# SPI_Relays.net
KiCad netlist of a schematic drawn in Altium Designer
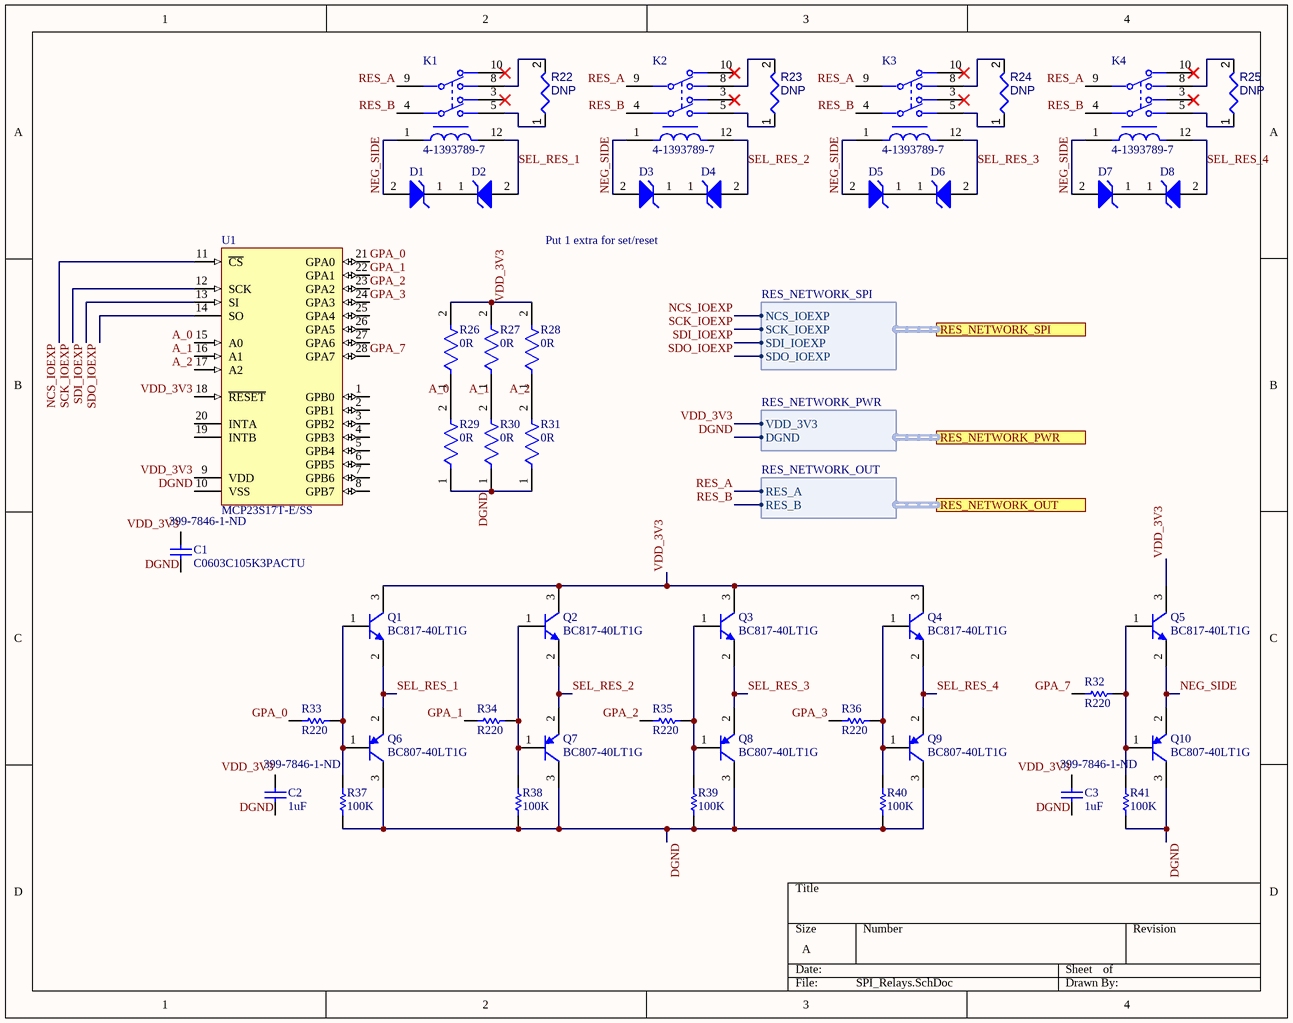
[diagram p0: SPI_Relays.SchDoc]

(export (version "E")
  (design (tool "Eeschema 10.0.6"))
  (components
    (comp (ref "C1")
      (value "C0603C105K3PACTU")
      (footprint "CAPC1608X95X35LL15T15")
      (fields
        (field (name "MANUFACTURER") "Kemet")
        (field (name "SUPPLIER PART NUMBER 1") "399-7846-1-ND")
        (field (name "TOLERANCE") "10%")
        (field (name "VOLTAGE") "25V")
      )
      (libsource (lib "Altium Content Vault") (part "CAP"))
    )
    (comp (ref "C2")
      (value "1uF")
      (footprint "CAPC1608X95X35LL15T15")
      (fields
        (field (name "MANUFACTURER") "Kemet")
        (field (name "PART NUMBER") "C0603C105K3PACTU")
        (field (name "SUPPLIER PART NUMBER 1") "399-7846-1-ND")
        (field (name "TOLERANCE") "10%")
      )
      (libsource (lib "Altium Content Vault") (part "CAP"))
    )
    (comp (ref "C3")
      (value "1uF")
      (footprint "CAPC1608X95X35LL15T15")
      (fields
        (field (name "MANUFACTURER") "Kemet")
        (field (name "PART NUMBER") "C0603C105K3PACTU")
        (field (name "SUPPLIER PART NUMBER 1") "399-7846-1-ND")
        (field (name "TOLERANCE") "10%")
      )
      (libsource (lib "Altium Content Vault") (part "CAP"))
    )
    (comp (ref "D1")
      (value "SZMM3Z6V2T1G")
      (footprint "ONSC-SOD-323-2-477-02_V")
      (description "Zener Voltage Regulator, 300 mW, 2-Pin SOD-323, Pb-Free, Tape and Reel")
      (fields (field (name "MANUFACTURER") "On Semiconductor"))
      (libsource (lib "Altium Content Vault") (part "ONSC-K1A2-2"))
    )
    (comp (ref "D2")
      (value "SZMM3Z6V2T1G")
      (footprint "ONSC-SOD-323-2-477-02_V")
      (description "Zener Voltage Regulator, 300 mW, 2-Pin SOD-323, Pb-Free, Tape and Reel")
      (fields (field (name "MANUFACTURER") "On Semiconductor"))
      (libsource (lib "Altium Content Vault") (part "ONSC-K1A2-2"))
    )
    (comp (ref "D3")
      (value "SZMM3Z6V2T1G")
      (footprint "ONSC-SOD-323-2-477-02_V")
      (description "Zener Voltage Regulator, 300 mW, 2-Pin SOD-323, Pb-Free, Tape and Reel")
      (fields (field (name "MANUFACTURER") "On Semiconductor"))
      (libsource (lib "Altium Content Vault") (part "ONSC-K1A2-2"))
    )
    (comp (ref "D4")
      (value "SZMM3Z6V2T1G")
      (footprint "ONSC-SOD-323-2-477-02_V")
      (description "Zener Voltage Regulator, 300 mW, 2-Pin SOD-323, Pb-Free, Tape and Reel")
      (fields (field (name "MANUFACTURER") "On Semiconductor"))
      (libsource (lib "Altium Content Vault") (part "ONSC-K1A2-2"))
    )
    (comp (ref "D5")
      (value "SZMM3Z6V2T1G")
      (footprint "ONSC-SOD-323-2-477-02_V")
      (description "Zener Voltage Regulator, 300 mW, 2-Pin SOD-323, Pb-Free, Tape and Reel")
      (fields (field (name "MANUFACTURER") "On Semiconductor"))
      (libsource (lib "Altium Content Vault") (part "ONSC-K1A2-2"))
    )
    (comp (ref "D6")
      (value "SZMM3Z6V2T1G")
      (footprint "ONSC-SOD-323-2-477-02_V")
      (description "Zener Voltage Regulator, 300 mW, 2-Pin SOD-323, Pb-Free, Tape and Reel")
      (fields (field (name "MANUFACTURER") "On Semiconductor"))
      (libsource (lib "Altium Content Vault") (part "ONSC-K1A2-2"))
    )
    (comp (ref "D7")
      (value "SZMM3Z6V2T1G")
      (footprint "ONSC-SOD-323-2-477-02_V")
      (description "Zener Voltage Regulator, 300 mW, 2-Pin SOD-323, Pb-Free, Tape and Reel")
      (fields (field (name "MANUFACTURER") "On Semiconductor"))
      (libsource (lib "Altium Content Vault") (part "ONSC-K1A2-2"))
    )
    (comp (ref "D8")
      (value "SZMM3Z6V2T1G")
      (footprint "ONSC-SOD-323-2-477-02_V")
      (description "Zener Voltage Regulator, 300 mW, 2-Pin SOD-323, Pb-Free, Tape and Reel")
      (fields (field (name "MANUFACTURER") "On Semiconductor"))
      (libsource (lib "Altium Content Vault") (part "ONSC-K1A2-2"))
    )
    (comp (ref "K1")
      (value "4-1393789-7")
      (footprint "FP-4-1393789-7-MFG")
      (description "RELAY GEN PURPOSE DPDT 2A 3VDC")
      (fields
        (field (name "MANUFACTURER") "TE")
        (field (name "OCTOPART") "https://octopart.com/4-1393789-7-te+connectivity-40938501")
      )
      (libsource (lib "Altium Content Vault") (part "0eb556c25f570307de68544099c8378"))
    )
    (comp (ref "K2")
      (value "4-1393789-7")
      (footprint "FP-4-1393789-7-MFG")
      (description "RELAY GEN PURPOSE DPDT 2A 3VDC")
      (fields
        (field (name "MANUFACTURER") "TE")
        (field (name "OCTOPART") "https://octopart.com/4-1393789-7-te+connectivity-40938501")
      )
      (libsource (lib "Altium Content Vault") (part "0eb556c25f570307de68544099c8378"))
    )
    (comp (ref "K3")
      (value "4-1393789-7")
      (footprint "FP-4-1393789-7-MFG")
      (description "RELAY GEN PURPOSE DPDT 2A 3VDC")
      (fields
        (field (name "MANUFACTURER") "TE")
        (field (name "OCTOPART") "https://octopart.com/4-1393789-7-te+connectivity-40938501")
      )
      (libsource (lib "Altium Content Vault") (part "0eb556c25f570307de68544099c8378"))
    )
    (comp (ref "K4")
      (value "4-1393789-7")
      (footprint "FP-4-1393789-7-MFG")
      (description "RELAY GEN PURPOSE DPDT 2A 3VDC")
      (fields
        (field (name "MANUFACTURER") "TE")
        (field (name "OCTOPART") "https://octopart.com/4-1393789-7-te+connectivity-40938501")
      )
      (libsource (lib "Altium Content Vault") (part "0eb556c25f570307de68544099c8378"))
    )
    (comp (ref "Q1")
      (value "BC817-40LT1G")
      (footprint "ONSC-SOT-23-3-318-08_V")
      (description "General Purpose Transistor, NPN Silicon, 3-Pin SOT-23, Pb-Free, Tape and Reel")
      (fields (field (name "MANUFACTURER") "On Semiconductor"))
      (libsource (lib "Altium Content Vault") (part "ONSC-NPN-B1E2C3-3"))
    )
    (comp (ref "Q2")
      (value "BC817-40LT1G")
      (footprint "ONSC-SOT-23-3-318-08_V")
      (description "General Purpose Transistor, NPN Silicon, 3-Pin SOT-23, Pb-Free, Tape and Reel")
      (fields (field (name "MANUFACTURER") "On Semiconductor"))
      (libsource (lib "Altium Content Vault") (part "ONSC-NPN-B1E2C3-3"))
    )
    (comp (ref "Q3")
      (value "BC817-40LT1G")
      (footprint "ONSC-SOT-23-3-318-08_V")
      (description "General Purpose Transistor, NPN Silicon, 3-Pin SOT-23, Pb-Free, Tape and Reel")
      (fields (field (name "MANUFACTURER") "On Semiconductor"))
      (libsource (lib "Altium Content Vault") (part "ONSC-NPN-B1E2C3-3"))
    )
    (comp (ref "Q4")
      (value "BC817-40LT1G")
      (footprint "ONSC-SOT-23-3-318-08_V")
      (description "General Purpose Transistor, NPN Silicon, 3-Pin SOT-23, Pb-Free, Tape and Reel")
      (fields (field (name "MANUFACTURER") "On Semiconductor"))
      (libsource (lib "Altium Content Vault") (part "ONSC-NPN-B1E2C3-3"))
    )
    (comp (ref "Q5")
      (value "BC817-40LT1G")
      (footprint "ONSC-SOT-23-3-318-08_V")
      (description "General Purpose Transistor, NPN Silicon, 3-Pin SOT-23, Pb-Free, Tape and Reel")
      (fields (field (name "MANUFACTURER") "On Semiconductor"))
      (libsource (lib "Altium Content Vault") (part "ONSC-NPN-B1E2C3-3"))
    )
    (comp (ref "Q6")
      (value "BC807-40LT1G")
      (footprint "ONSC-SOT-23-3-318-08_V")
      (description "General Purpose Transistor, PNP Silicon, 3-Pin SOT-23, Pb-Free, Tape and Reel")
      (fields (field (name "MANUFACTURER") "On Semiconductor"))
      (libsource (lib "Altium Content Vault") (part "ONSC-PNP-B1E2C3-3"))
    )
    (comp (ref "Q7")
      (value "BC807-40LT1G")
      (footprint "ONSC-SOT-23-3-318-08_V")
      (description "General Purpose Transistor, PNP Silicon, 3-Pin SOT-23, Pb-Free, Tape and Reel")
      (fields (field (name "MANUFACTURER") "On Semiconductor"))
      (libsource (lib "Altium Content Vault") (part "ONSC-PNP-B1E2C3-3"))
    )
    (comp (ref "Q8")
      (value "BC807-40LT1G")
      (footprint "ONSC-SOT-23-3-318-08_V")
      (description "General Purpose Transistor, PNP Silicon, 3-Pin SOT-23, Pb-Free, Tape and Reel")
      (fields (field (name "MANUFACTURER") "On Semiconductor"))
      (libsource (lib "Altium Content Vault") (part "ONSC-PNP-B1E2C3-3"))
    )
    (comp (ref "Q9")
      (value "BC807-40LT1G")
      (footprint "ONSC-SOT-23-3-318-08_V")
      (description "General Purpose Transistor, PNP Silicon, 3-Pin SOT-23, Pb-Free, Tape and Reel")
      (fields (field (name "MANUFACTURER") "On Semiconductor"))
      (libsource (lib "Altium Content Vault") (part "ONSC-PNP-B1E2C3-3"))
    )
    (comp (ref "Q10")
      (value "BC807-40LT1G")
      (footprint "ONSC-SOT-23-3-318-08_V")
      (description "General Purpose Transistor, PNP Silicon, 3-Pin SOT-23, Pb-Free, Tape and Reel")
      (fields (field (name "MANUFACTURER") "On Semiconductor"))
      (libsource (lib "Altium Content Vault") (part "ONSC-PNP-B1E2C3-3"))
    )
    (comp (ref "R22")
      (value "DNP")
      (footprint "RESC1608X55X25ML10T15")
      (description "do not place")
      (libsource (lib "Lovro's workspace") (part "RES-2"))
    )
    (comp (ref "R23")
      (value "DNP")
      (footprint "RESC1608X55X25ML10T15")
      (description "do not place")
      (libsource (lib "Lovro's workspace") (part "RES-2"))
    )
    (comp (ref "R24")
      (value "DNP")
      (footprint "RESC1608X55X25ML10T15")
      (description "do not place")
      (libsource (lib "Lovro's workspace") (part "RES-2"))
    )
    (comp (ref "R25")
      (value "DNP")
      (footprint "RESC1608X55X25ML10T15")
      (description "do not place")
      (libsource (lib "Lovro's workspace") (part "RES-2"))
    )
    (comp (ref "R26")
      (value "0R")
      (footprint "FP-CR0603-MFG")
      (description "Thick Film Chip Resistors 0603 0Ω 0.1W 5%")
      (fields (field (name "TOLERANCE") "1%"))
      (libsource (lib "Altium Content Vault") (part "1029c3af85768c4190bb7ad29bc67b5"))
    )
    (comp (ref "R27")
      (value "0R")
      (footprint "FP-CR0603-MFG")
      (description "Thick Film Chip Resistors 0603 0Ω 0.1W 5%")
      (fields (field (name "TOLERANCE") "1%"))
      (libsource (lib "Altium Content Vault") (part "1029c3af85768c4190bb7ad29bc67b5"))
    )
    (comp (ref "R28")
      (value "0R")
      (footprint "FP-CR0603-MFG")
      (description "Thick Film Chip Resistors 0603 0Ω 0.1W 5%")
      (fields (field (name "TOLERANCE") "1%"))
      (libsource (lib "Altium Content Vault") (part "1029c3af85768c4190bb7ad29bc67b5"))
    )
    (comp (ref "R29")
      (value "0R")
      (footprint "FP-CR0603-MFG")
      (description "Thick Film Chip Resistors 0603 0Ω 0.1W 5%")
      (fields (field (name "TOLERANCE") "1%"))
      (libsource (lib "Altium Content Vault") (part "1029c3af85768c4190bb7ad29bc67b5"))
    )
    (comp (ref "R30")
      (value "0R")
      (footprint "FP-CR0603-MFG")
      (description "Thick Film Chip Resistors 0603 0Ω 0.1W 5%")
      (fields (field (name "TOLERANCE") "1%"))
      (libsource (lib "Altium Content Vault") (part "1029c3af85768c4190bb7ad29bc67b5"))
    )
    (comp (ref "R31")
      (value "0R")
      (footprint "FP-CR0603-MFG")
      (description "Thick Film Chip Resistors 0603 0Ω 0.1W 5%")
      (fields (field (name "TOLERANCE") "1%"))
      (libsource (lib "Altium Content Vault") (part "1029c3af85768c4190bb7ad29bc67b5"))
    )
    (comp (ref "R32")
      (value "R220")
      (footprint "RESC1609X50X30LL10T20")
      (fields (field (name "PART NUMBER") "CRCW0603220RFKEA") (field (name "MANUFACTURER") "Vishay Dale"))
      (libsource (lib "Altium Content Vault") (part "RES"))
    )
    (comp (ref "R33")
      (value "R220")
      (footprint "RESC1609X50X30LL10T20")
      (fields (field (name "PART NUMBER") "CRCW0603220RFKEA") (field (name "MANUFACTURER") "Vishay Dale"))
      (libsource (lib "Altium Content Vault") (part "RES"))
    )
    (comp (ref "R34")
      (value "R220")
      (footprint "RESC1609X50X30LL10T20")
      (fields (field (name "PART NUMBER") "CRCW0603220RFKEA") (field (name "MANUFACTURER") "Vishay Dale"))
      (libsource (lib "Altium Content Vault") (part "RES"))
    )
    (comp (ref "R35")
      (value "R220")
      (footprint "RESC1609X50X30LL10T20")
      (fields (field (name "PART NUMBER") "CRCW0603220RFKEA") (field (name "MANUFACTURER") "Vishay Dale"))
      (libsource (lib "Altium Content Vault") (part "RES"))
    )
    (comp (ref "R36")
      (value "R220")
      (footprint "RESC1609X50X30LL10T20")
      (fields (field (name "PART NUMBER") "CRCW0603220RFKEA") (field (name "MANUFACTURER") "Vishay Dale"))
      (libsource (lib "Altium Content Vault") (part "RES"))
    )
    (comp (ref "R37")
      (value "100K")
      (footprint "RESC1608X55X25ML10T15")
      (description "Chip Resistor, 100 KOhm, +/- 1%, 0.1 W, -55 to 155 degC, 0603 (1608 Metric), RoHS, Tape and Reel")
      (fields (field (name "MANUFACTURER") "Yageo") (field (name "TOLERANCE") "1%"))
      (libsource (lib "Altium Content Vault") (part "RES-2"))
    )
    (comp (ref "R38")
      (value "100K")
      (footprint "RESC1608X55X25ML10T15")
      (description "Chip Resistor, 100 KOhm, +/- 1%, 0.1 W, -55 to 155 degC, 0603 (1608 Metric), RoHS, Tape and Reel")
      (fields (field (name "MANUFACTURER") "Yageo") (field (name "TOLERANCE") "1%"))
      (libsource (lib "Altium Content Vault") (part "RES-2"))
    )
    (comp (ref "R39")
      (value "100K")
      (footprint "RESC1608X55X25ML10T15")
      (description "Chip Resistor, 100 KOhm, +/- 1%, 0.1 W, -55 to 155 degC, 0603 (1608 Metric), RoHS, Tape and Reel")
      (fields (field (name "MANUFACTURER") "Yageo") (field (name "TOLERANCE") "1%"))
      (libsource (lib "Altium Content Vault") (part "RES-2"))
    )
    (comp (ref "R40")
      (value "100K")
      (footprint "RESC1608X55X25ML10T15")
      (description "Chip Resistor, 100 KOhm, +/- 1%, 0.1 W, -55 to 155 degC, 0603 (1608 Metric), RoHS, Tape and Reel")
      (fields (field (name "MANUFACTURER") "Yageo") (field (name "TOLERANCE") "1%"))
      (libsource (lib "Altium Content Vault") (part "RES-2"))
    )
    (comp (ref "R41")
      (value "100K")
      (footprint "RESC1608X55X25ML10T15")
      (description "Chip Resistor, 100 KOhm, +/- 1%, 0.1 W, -55 to 155 degC, 0603 (1608 Metric), RoHS, Tape and Reel")
      (fields (field (name "MANUFACTURER") "Yageo") (field (name "TOLERANCE") "1%"))
      (libsource (lib "Altium Content Vault") (part "RES-2"))
    )
    (comp (ref "U1")
      (value "MCP23S17T-E/SS")
      (footprint "SSOP-SS28_M")
      (description "16-Bit I/O Expander with Serial Interface, 28-Pin SSOP, Extended Temperature, Tape and Reel")
      (libsource (lib "Altium Content Vault") (part "PR-BUSIC-MCP23S17-28"))
    )
  )
  (nets
    (net (code "4") (name "/A_0") (class "Default")
      (node (ref "R26") (pin "1") (pinfunction "1_1") (pintype "passive"))
      (node (ref "R29") (pin "2") (pinfunction "2_2") (pintype "passive"))
      (node (ref "U1") (pin "15") (pinfunction "A0_15") (pintype "input"))
    )
    (net (code "5") (name "/A_1") (class "Default")
      (node (ref "R27") (pin "1") (pinfunction "1_1") (pintype "passive"))
      (node (ref "R30") (pin "2") (pinfunction "2_2") (pintype "passive"))
      (node (ref "U1") (pin "16") (pinfunction "A1_16") (pintype "input"))
    )
    (net (code "6") (name "/A_2") (class "Default")
      (node (ref "R28") (pin "1") (pinfunction "1_1") (pintype "passive"))
      (node (ref "R31") (pin "2") (pinfunction "2_2") (pintype "passive"))
      (node (ref "U1") (pin "17") (pinfunction "A2_17") (pintype "input"))
    )
    (net (code "7") (name "/DGND") (class "Default")
      (node (ref "C1") (pin "1") (pinfunction "1_1") (pintype "passive"))
      (node (ref "C2") (pin "1") (pinfunction "1_1") (pintype "passive"))
      (node (ref "C3") (pin "1") (pinfunction "1_1") (pintype "passive"))
      (node (ref "Q10") (pin "3") (pinfunction "C_3") (pintype "passive"))
      (node (ref "Q6") (pin "3") (pinfunction "C_3") (pintype "passive"))
      (node (ref "Q7") (pin "3") (pinfunction "C_3") (pintype "passive"))
      (node (ref "Q8") (pin "3") (pinfunction "C_3") (pintype "passive"))
      (node (ref "Q9") (pin "3") (pinfunction "C_3") (pintype "passive"))
      (node (ref "R29") (pin "1") (pinfunction "1_1") (pintype "passive"))
      (node (ref "R30") (pin "1") (pinfunction "1_1") (pintype "passive"))
      (node (ref "R31") (pin "1") (pinfunction "1_1") (pintype "passive"))
      (node (ref "R37") (pin "1") (pinfunction "1_1") (pintype "passive"))
      (node (ref "R38") (pin "1") (pinfunction "1_1") (pintype "passive"))
      (node (ref "R39") (pin "1") (pinfunction "1_1") (pintype "passive"))
      (node (ref "R40") (pin "1") (pinfunction "1_1") (pintype "passive"))
      (node (ref "R41") (pin "1") (pinfunction "1_1") (pintype "passive"))
      (node (ref "U1") (pin "10") (pinfunction "VSS_10") (pintype "power_in"))
    )
    (net (code "8") (name "/GPA_0") (class "Default")
      (node (ref "R33") (pin "1") (pinfunction "1_1") (pintype "passive"))
      (node (ref "U1") (pin "21") (pinfunction "GPA0_21") (pintype "bidirectional"))
    )
    (net (code "9") (name "/GPA_1") (class "Default")
      (node (ref "R34") (pin "1") (pinfunction "1_1") (pintype "passive"))
      (node (ref "U1") (pin "22") (pinfunction "GPA1_22") (pintype "bidirectional"))
    )
    (net (code "10") (name "/GPA_2") (class "Default")
      (node (ref "R35") (pin "1") (pinfunction "1_1") (pintype "passive"))
      (node (ref "U1") (pin "23") (pinfunction "GPA2_23") (pintype "bidirectional"))
    )
    (net (code "11") (name "/GPA_3") (class "Default")
      (node (ref "R36") (pin "1") (pinfunction "1_1") (pintype "passive"))
      (node (ref "U1") (pin "24") (pinfunction "GPA3_24") (pintype "bidirectional"))
    )
    (net (code "12") (name "/GPA_7") (class "Default")
      (node (ref "R32") (pin "1") (pinfunction "1_1") (pintype "passive"))
      (node (ref "U1") (pin "28") (pinfunction "GPA7_28") (pintype "bidirectional"))
    )
    (net (code "13") (name "/NCS_IOEXP") (class "Default")
      (node (ref "U1") (pin "11") (pinfunction "~{CS}_11") (pintype "input"))
    )
    (net (code "14") (name "/NEG_SIDE") (class "Default")
      (node (ref "D1") (pin "2") (pinfunction "A_2") (pintype "passive"))
      (node (ref "D3") (pin "2") (pinfunction "A_2") (pintype "passive"))
      (node (ref "D5") (pin "2") (pinfunction "A_2") (pintype "passive"))
      (node (ref "D7") (pin "2") (pinfunction "A_2") (pintype "passive"))
      (node (ref "K1") (pin "1") (pinfunction "1_1") (pintype "passive"))
      (node (ref "K2") (pin "1") (pinfunction "1_1") (pintype "passive"))
      (node (ref "K3") (pin "1") (pinfunction "1_1") (pintype "passive"))
      (node (ref "K4") (pin "1") (pinfunction "1_1") (pintype "passive"))
      (node (ref "Q10") (pin "2") (pinfunction "E_2") (pintype "passive"))
      (node (ref "Q5") (pin "2") (pinfunction "E_2") (pintype "passive"))
    )
    (net (code "15") (name "/RES_A") (class "Default")
      (node (ref "K1") (pin "9") (pinfunction "9_9") (pintype "passive"))
      (node (ref "K2") (pin "9") (pinfunction "9_9") (pintype "passive"))
      (node (ref "K3") (pin "9") (pinfunction "9_9") (pintype "passive"))
      (node (ref "K4") (pin "9") (pinfunction "9_9") (pintype "passive"))
    )
    (net (code "16") (name "/RES_B") (class "Default")
      (node (ref "K1") (pin "4") (pinfunction "4_4") (pintype "passive"))
      (node (ref "K2") (pin "4") (pinfunction "4_4") (pintype "passive"))
      (node (ref "K3") (pin "4") (pinfunction "4_4") (pintype "passive"))
      (node (ref "K4") (pin "4") (pinfunction "4_4") (pintype "passive"))
    )
    (net (code "17") (name "/SCK_IOEXP") (class "Default")
      (node (ref "U1") (pin "12") (pinfunction "SCK_12") (pintype "input"))
    )
    (net (code "18") (name "/SDI_IOEXP") (class "Default")
      (node (ref "U1") (pin "13") (pinfunction "SI_13") (pintype "input"))
    )
    (net (code "19") (name "/SDO_IOEXP") (class "Default")
      (node (ref "U1") (pin "14") (pinfunction "SO_14") (pintype "tri_state"))
    )
    (net (code "20") (name "/SEL_RES_1") (class "Default")
      (node (ref "D2") (pin "2") (pinfunction "A_2") (pintype "passive"))
      (node (ref "K1") (pin "12") (pinfunction "12_12") (pintype "passive"))
      (node (ref "Q1") (pin "2") (pinfunction "E_2") (pintype "passive"))
      (node (ref "Q6") (pin "2") (pinfunction "E_2") (pintype "passive"))
    )
    (net (code "21") (name "/SEL_RES_2") (class "Default")
      (node (ref "D4") (pin "2") (pinfunction "A_2") (pintype "passive"))
      (node (ref "K2") (pin "12") (pinfunction "12_12") (pintype "passive"))
      (node (ref "Q2") (pin "2") (pinfunction "E_2") (pintype "passive"))
      (node (ref "Q7") (pin "2") (pinfunction "E_2") (pintype "passive"))
    )
    (net (code "22") (name "/SEL_RES_3") (class "Default")
      (node (ref "D6") (pin "2") (pinfunction "A_2") (pintype "passive"))
      (node (ref "K3") (pin "12") (pinfunction "12_12") (pintype "passive"))
      (node (ref "Q3") (pin "2") (pinfunction "E_2") (pintype "passive"))
      (node (ref "Q8") (pin "2") (pinfunction "E_2") (pintype "passive"))
    )
    (net (code "23") (name "/SEL_RES_4") (class "Default")
      (node (ref "D8") (pin "2") (pinfunction "A_2") (pintype "passive"))
      (node (ref "K4") (pin "12") (pinfunction "12_12") (pintype "passive"))
      (node (ref "Q4") (pin "2") (pinfunction "E_2") (pintype "passive"))
      (node (ref "Q9") (pin "2") (pinfunction "E_2") (pintype "passive"))
    )
    (net (code "24") (name "/VDD_3V3") (class "Default")
      (node (ref "C1") (pin "2") (pinfunction "2_2") (pintype "passive"))
      (node (ref "C2") (pin "2") (pinfunction "2_2") (pintype "passive"))
      (node (ref "C3") (pin "2") (pinfunction "2_2") (pintype "passive"))
      (node (ref "Q1") (pin "3") (pinfunction "C_3") (pintype "passive"))
      (node (ref "Q2") (pin "3") (pinfunction "C_3") (pintype "passive"))
      (node (ref "Q3") (pin "3") (pinfunction "C_3") (pintype "passive"))
      (node (ref "Q4") (pin "3") (pinfunction "C_3") (pintype "passive"))
      (node (ref "Q5") (pin "3") (pinfunction "C_3") (pintype "passive"))
      (node (ref "R26") (pin "2") (pinfunction "2_2") (pintype "passive"))
      (node (ref "R27") (pin "2") (pinfunction "2_2") (pintype "passive"))
      (node (ref "R28") (pin "2") (pinfunction "2_2") (pintype "passive"))
      (node (ref "U1") (pin "18") (pinfunction "~{RESET}_18") (pintype "input"))
      (node (ref "U1") (pin "9") (pinfunction "VDD_9") (pintype "power_in"))
    )
    (net (code "28") (name "Net-(D1-K)") (class "Default")
      (node (ref "D1") (pin "1") (pinfunction "K_1") (pintype "passive"))
      (node (ref "D2") (pin "1") (pinfunction "K_1") (pintype "passive"))
    )
    (net (code "29") (name "Net-(D3-K)") (class "Default")
      (node (ref "D3") (pin "1") (pinfunction "K_1") (pintype "passive"))
      (node (ref "D4") (pin "1") (pinfunction "K_1") (pintype "passive"))
    )
    (net (code "30") (name "Net-(D5-K)") (class "Default")
      (node (ref "D5") (pin "1") (pinfunction "K_1") (pintype "passive"))
      (node (ref "D6") (pin "1") (pinfunction "K_1") (pintype "passive"))
    )
    (net (code "31") (name "Net-(D7-K)") (class "Default")
      (node (ref "D7") (pin "1") (pinfunction "K_1") (pintype "passive"))
      (node (ref "D8") (pin "1") (pinfunction "K_1") (pintype "passive"))
    )
    (net (code "32") (name "Net-(K1-Pad5)") (class "Default")
      (node (ref "K1") (pin "5") (pinfunction "5_5") (pintype "passive"))
      (node (ref "R22") (pin "1") (pinfunction "1_1") (pintype "passive"))
    )
    (net (code "33") (name "Net-(K1-Pad8)") (class "Default")
      (node (ref "K1") (pin "8") (pinfunction "8_8") (pintype "passive"))
      (node (ref "R22") (pin "2") (pinfunction "2_2") (pintype "passive"))
    )
    (net (code "34") (name "Net-(K2-Pad5)") (class "Default")
      (node (ref "K2") (pin "5") (pinfunction "5_5") (pintype "passive"))
      (node (ref "R23") (pin "1") (pinfunction "1_1") (pintype "passive"))
    )
    (net (code "35") (name "Net-(K2-Pad8)") (class "Default")
      (node (ref "K2") (pin "8") (pinfunction "8_8") (pintype "passive"))
      (node (ref "R23") (pin "2") (pinfunction "2_2") (pintype "passive"))
    )
    (net (code "36") (name "Net-(K3-Pad5)") (class "Default")
      (node (ref "K3") (pin "5") (pinfunction "5_5") (pintype "passive"))
      (node (ref "R24") (pin "1") (pinfunction "1_1") (pintype "passive"))
    )
    (net (code "37") (name "Net-(K3-Pad8)") (class "Default")
      (node (ref "K3") (pin "8") (pinfunction "8_8") (pintype "passive"))
      (node (ref "R24") (pin "2") (pinfunction "2_2") (pintype "passive"))
    )
    (net (code "38") (name "Net-(K4-Pad5)") (class "Default")
      (node (ref "K4") (pin "5") (pinfunction "5_5") (pintype "passive"))
      (node (ref "R25") (pin "1") (pinfunction "1_1") (pintype "passive"))
    )
    (net (code "39") (name "Net-(K4-Pad8)") (class "Default")
      (node (ref "K4") (pin "8") (pinfunction "8_8") (pintype "passive"))
      (node (ref "R25") (pin "2") (pinfunction "2_2") (pintype "passive"))
    )
    (net (code "40") (name "Net-(Q1-B)") (class "Default")
      (node (ref "Q1") (pin "1") (pinfunction "B_1") (pintype "passive"))
      (node (ref "Q6") (pin "1") (pinfunction "B_1") (pintype "passive"))
      (node (ref "R33") (pin "2") (pinfunction "2_2") (pintype "passive"))
      (node (ref "R37") (pin "2") (pinfunction "2_2") (pintype "passive"))
    )
    (net (code "41") (name "Net-(Q2-B)") (class "Default")
      (node (ref "Q2") (pin "1") (pinfunction "B_1") (pintype "passive"))
      (node (ref "Q7") (pin "1") (pinfunction "B_1") (pintype "passive"))
      (node (ref "R34") (pin "2") (pinfunction "2_2") (pintype "passive"))
      (node (ref "R38") (pin "2") (pinfunction "2_2") (pintype "passive"))
    )
    (net (code "42") (name "Net-(Q3-B)") (class "Default")
      (node (ref "Q3") (pin "1") (pinfunction "B_1") (pintype "passive"))
      (node (ref "Q8") (pin "1") (pinfunction "B_1") (pintype "passive"))
      (node (ref "R35") (pin "2") (pinfunction "2_2") (pintype "passive"))
      (node (ref "R39") (pin "2") (pinfunction "2_2") (pintype "passive"))
    )
    (net (code "43") (name "Net-(Q4-B)") (class "Default")
      (node (ref "Q4") (pin "1") (pinfunction "B_1") (pintype "passive"))
      (node (ref "Q9") (pin "1") (pinfunction "B_1") (pintype "passive"))
      (node (ref "R36") (pin "2") (pinfunction "2_2") (pintype "passive"))
      (node (ref "R40") (pin "2") (pinfunction "2_2") (pintype "passive"))
    )
    (net (code "44") (name "Net-(Q10-B)") (class "Default")
      (node (ref "Q10") (pin "1") (pinfunction "B_1") (pintype "passive"))
      (node (ref "Q5") (pin "1") (pinfunction "B_1") (pintype "passive"))
      (node (ref "R32") (pin "2") (pinfunction "2_2") (pintype "passive"))
      (node (ref "R41") (pin "2") (pinfunction "2_2") (pintype "passive"))
    )
    (net (code "45") (name "unconnected-(K1-Pad3)") (class "Default")
      (node (ref "K1") (pin "3") (pinfunction "3_3") (pintype "passive+no_connect"))
    )
    (net (code "46") (name "unconnected-(K1-Pad10)") (class "Default")
      (node (ref "K1") (pin "10") (pinfunction "10_10") (pintype "passive+no_connect"))
    )
    (net (code "47") (name "unconnected-(K2-Pad3)") (class "Default")
      (node (ref "K2") (pin "3") (pinfunction "3_3") (pintype "passive+no_connect"))
    )
    (net (code "48") (name "unconnected-(K2-Pad10)") (class "Default")
      (node (ref "K2") (pin "10") (pinfunction "10_10") (pintype "passive+no_connect"))
    )
    (net (code "49") (name "unconnected-(K3-Pad3)") (class "Default")
      (node (ref "K3") (pin "3") (pinfunction "3_3") (pintype "passive+no_connect"))
    )
    (net (code "50") (name "unconnected-(K3-Pad10)") (class "Default")
      (node (ref "K3") (pin "10") (pinfunction "10_10") (pintype "passive+no_connect"))
    )
    (net (code "51") (name "unconnected-(K4-Pad3)") (class "Default")
      (node (ref "K4") (pin "3") (pinfunction "3_3") (pintype "passive+no_connect"))
    )
    (net (code "52") (name "unconnected-(K4-Pad10)") (class "Default")
      (node (ref "K4") (pin "10") (pinfunction "10_10") (pintype "passive+no_connect"))
    )
    (net (code "53") (name "unconnected-(U1-GPA4-Pad25)") (class "Default")
      (node (ref "U1") (pin "25") (pinfunction "GPA4_25") (pintype "bidirectional"))
    )
    (net (code "54") (name "unconnected-(U1-GPA5-Pad26)") (class "Default")
      (node (ref "U1") (pin "26") (pinfunction "GPA5_26") (pintype "bidirectional"))
    )
    (net (code "55") (name "unconnected-(U1-GPA6-Pad27)") (class "Default")
      (node (ref "U1") (pin "27") (pinfunction "GPA6_27") (pintype "bidirectional"))
    )
    (net (code "56") (name "unconnected-(U1-GPB0-Pad1)") (class "Default")
      (node (ref "U1") (pin "1") (pinfunction "GPB0_1") (pintype "bidirectional"))
    )
    (net (code "57") (name "unconnected-(U1-GPB1-Pad2)") (class "Default")
      (node (ref "U1") (pin "2") (pinfunction "GPB1_2") (pintype "bidirectional"))
    )
    (net (code "58") (name "unconnected-(U1-GPB2-Pad3)") (class "Default")
      (node (ref "U1") (pin "3") (pinfunction "GPB2_3") (pintype "bidirectional"))
    )
    (net (code "59") (name "unconnected-(U1-GPB3-Pad4)") (class "Default")
      (node (ref "U1") (pin "4") (pinfunction "GPB3_4") (pintype "bidirectional"))
    )
    (net (code "60") (name "unconnected-(U1-GPB4-Pad5)") (class "Default")
      (node (ref "U1") (pin "5") (pinfunction "GPB4_5") (pintype "bidirectional"))
    )
    (net (code "61") (name "unconnected-(U1-GPB5-Pad6)") (class "Default")
      (node (ref "U1") (pin "6") (pinfunction "GPB5_6") (pintype "bidirectional"))
    )
    (net (code "62") (name "unconnected-(U1-GPB6-Pad7)") (class "Default")
      (node (ref "U1") (pin "7") (pinfunction "GPB6_7") (pintype "bidirectional"))
    )
    (net (code "63") (name "unconnected-(U1-GPB7-Pad8)") (class "Default")
      (node (ref "U1") (pin "8") (pinfunction "GPB7_8") (pintype "bidirectional"))
    )
    (net (code "64") (name "unconnected-(U1-INTA-Pad20)") (class "Default")
      (node (ref "U1") (pin "20") (pinfunction "INTA_20") (pintype "open_collector"))
    )
    (net (code "65") (name "unconnected-(U1-INTB-Pad19)") (class "Default")
      (node (ref "U1") (pin "19") (pinfunction "INTB_19") (pintype "open_collector"))
    )
  )
)
